# faun-node-connector.net
KiCad netlist of a schematic drawn in EAGLE
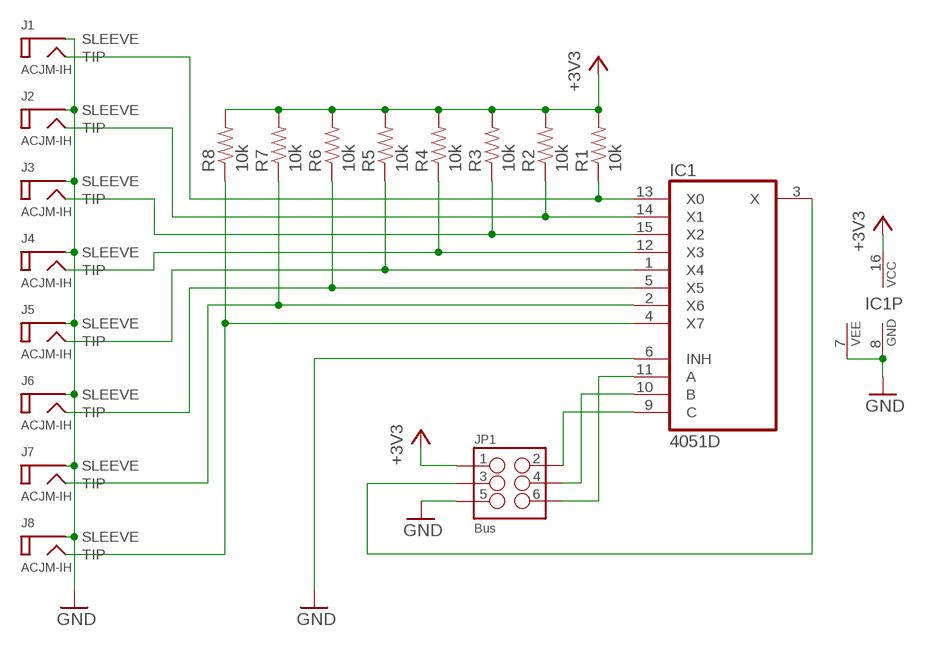
[diagram p0: schematic, sheet 1]

(export (version "E")
  (design (tool "Eeschema 10.0.6"))
  (components
    (comp (ref "IC1")
      (value "4051D")
      (footprint "eagle-import:SO16")
      (libsource (lib "eagle-import") (part "4051D"))
    )
    (comp (ref "J1")
      (value "ACJM-IH")
      (footprint "eagle-import:ACJM-IH")
      (libsource (lib "eagle-import") (part "ACJM-IH"))
    )
    (comp (ref "J2")
      (value "ACJM-IH")
      (footprint "eagle-import:ACJM-IH")
      (libsource (lib "eagle-import") (part "ACJM-IH"))
    )
    (comp (ref "J3")
      (value "ACJM-IH")
      (footprint "eagle-import:ACJM-IH")
      (libsource (lib "eagle-import") (part "ACJM-IH"))
    )
    (comp (ref "J4")
      (value "ACJM-IH")
      (footprint "eagle-import:ACJM-IH")
      (libsource (lib "eagle-import") (part "ACJM-IH"))
    )
    (comp (ref "J5")
      (value "ACJM-IH")
      (footprint "eagle-import:ACJM-IH")
      (libsource (lib "eagle-import") (part "ACJM-IH"))
    )
    (comp (ref "J6")
      (value "ACJM-IH")
      (footprint "eagle-import:ACJM-IH")
      (libsource (lib "eagle-import") (part "ACJM-IH"))
    )
    (comp (ref "J7")
      (value "ACJM-IH")
      (footprint "eagle-import:ACJM-IH")
      (libsource (lib "eagle-import") (part "ACJM-IH"))
    )
    (comp (ref "J8")
      (value "ACJM-IH")
      (footprint "eagle-import:ACJM-IH")
      (libsource (lib "eagle-import") (part "ACJM-IH"))
    )
    (comp (ref "JP1")
      (value "Bus")
      (footprint "eagle-import:2X3")
      (libsource (lib "eagle-import") (part "M03X22X3_SILK_SM"))
    )
    (comp (ref "R1")
      (value "10k")
      (footprint "eagle-import:1206")
      (libsource (lib "eagle-import") (part "RESISTOR1206"))
    )
    (comp (ref "R2")
      (value "10k")
      (footprint "eagle-import:1206")
      (libsource (lib "eagle-import") (part "RESISTOR1206"))
    )
    (comp (ref "R3")
      (value "10k")
      (footprint "eagle-import:1206")
      (libsource (lib "eagle-import") (part "RESISTOR1206"))
    )
    (comp (ref "R4")
      (value "10k")
      (footprint "eagle-import:1206")
      (libsource (lib "eagle-import") (part "RESISTOR1206"))
    )
    (comp (ref "R5")
      (value "10k")
      (footprint "eagle-import:1206")
      (libsource (lib "eagle-import") (part "RESISTOR1206"))
    )
    (comp (ref "R6")
      (value "10k")
      (footprint "eagle-import:1206")
      (libsource (lib "eagle-import") (part "RESISTOR1206"))
    )
    (comp (ref "R7")
      (value "10k")
      (footprint "eagle-import:1206")
      (libsource (lib "eagle-import") (part "RESISTOR1206"))
    )
    (comp (ref "R8")
      (value "10k")
      (footprint "eagle-import:1206")
      (libsource (lib "eagle-import") (part "RESISTOR1206"))
    )
  )
  (nets
    (net (code "1") (name "+3V3") (class "Default")
      (node (ref "IC1") (pin "16") (pinfunction "VCC_16") (pintype "power_in"))
      (node (ref "JP1") (pin "1") (pinfunction "1_1") (pintype "bidirectional"))
      (node (ref "R1") (pin "2") (pinfunction "2_2") (pintype "passive"))
      (node (ref "R2") (pin "2") (pinfunction "2_2") (pintype "passive"))
      (node (ref "R3") (pin "2") (pinfunction "2_2") (pintype "passive"))
      (node (ref "R4") (pin "2") (pinfunction "2_2") (pintype "passive"))
      (node (ref "R5") (pin "2") (pinfunction "2_2") (pintype "passive"))
      (node (ref "R6") (pin "2") (pinfunction "2_2") (pintype "passive"))
      (node (ref "R7") (pin "2") (pinfunction "2_2") (pintype "passive"))
      (node (ref "R8") (pin "2") (pinfunction "2_2") (pintype "passive"))
    )
    (net (code "2") (name "GND") (class "Default")
      (node (ref "IC1") (pin "6") (pinfunction "INH_6") (pintype "input"))
      (node (ref "IC1") (pin "7") (pinfunction "VEE_7") (pintype "power_in"))
      (node (ref "IC1") (pin "8") (pinfunction "GND_8") (pintype "power_in"))
      (node (ref "J1") (pin "SLEEVE@1") (pinfunction "SLEEVE_SLEEVE@1") (pintype "bidirectional"))
      (node (ref "J1") (pin "SLEEVE@2") (pinfunction "SLEEVE_SLEEVE@2") (pintype "bidirectional"))
      (node (ref "J2") (pin "SLEEVE@1") (pinfunction "SLEEVE_SLEEVE@1") (pintype "bidirectional"))
      (node (ref "J2") (pin "SLEEVE@2") (pinfunction "SLEEVE_SLEEVE@2") (pintype "bidirectional"))
      (node (ref "J3") (pin "SLEEVE@1") (pinfunction "SLEEVE_SLEEVE@1") (pintype "bidirectional"))
      (node (ref "J3") (pin "SLEEVE@2") (pinfunction "SLEEVE_SLEEVE@2") (pintype "bidirectional"))
      (node (ref "J4") (pin "SLEEVE@1") (pinfunction "SLEEVE_SLEEVE@1") (pintype "bidirectional"))
      (node (ref "J4") (pin "SLEEVE@2") (pinfunction "SLEEVE_SLEEVE@2") (pintype "bidirectional"))
      (node (ref "J5") (pin "SLEEVE@1") (pinfunction "SLEEVE_SLEEVE@1") (pintype "bidirectional"))
      (node (ref "J5") (pin "SLEEVE@2") (pinfunction "SLEEVE_SLEEVE@2") (pintype "bidirectional"))
      (node (ref "J6") (pin "SLEEVE@1") (pinfunction "SLEEVE_SLEEVE@1") (pintype "bidirectional"))
      (node (ref "J6") (pin "SLEEVE@2") (pinfunction "SLEEVE_SLEEVE@2") (pintype "bidirectional"))
      (node (ref "J7") (pin "SLEEVE@1") (pinfunction "SLEEVE_SLEEVE@1") (pintype "bidirectional"))
      (node (ref "J7") (pin "SLEEVE@2") (pinfunction "SLEEVE_SLEEVE@2") (pintype "bidirectional"))
      (node (ref "J8") (pin "SLEEVE@1") (pinfunction "SLEEVE_SLEEVE@1") (pintype "bidirectional"))
      (node (ref "J8") (pin "SLEEVE@2") (pinfunction "SLEEVE_SLEEVE@2") (pintype "bidirectional"))
      (node (ref "JP1") (pin "5") (pinfunction "5_5") (pintype "bidirectional"))
    )
    (net (code "3") (name "Net-(IC1A-A)") (class "Default")
      (node (ref "IC1") (pin "11") (pinfunction "A_11") (pintype "input"))
      (node (ref "JP1") (pin "6") (pinfunction "6_6") (pintype "bidirectional"))
    )
    (net (code "4") (name "Net-(IC1A-B)") (class "Default")
      (node (ref "IC1") (pin "10") (pinfunction "B_10") (pintype "input"))
      (node (ref "JP1") (pin "4") (pinfunction "4_4") (pintype "bidirectional"))
    )
    (net (code "5") (name "Net-(IC1A-C)") (class "Default")
      (node (ref "IC1") (pin "9") (pinfunction "C_9") (pintype "input"))
      (node (ref "JP1") (pin "2") (pinfunction "2_2") (pintype "bidirectional"))
    )
    (net (code "6") (name "Net-(IC1A-X)") (class "Default")
      (node (ref "IC1") (pin "3") (pinfunction "X_3") (pintype "bidirectional"))
      (node (ref "JP1") (pin "3") (pinfunction "3_3") (pintype "bidirectional"))
    )
    (net (code "7") (name "Net-(IC1A-X0)") (class "Default")
      (node (ref "IC1") (pin "13") (pinfunction "X0_13") (pintype "bidirectional"))
      (node (ref "J1") (pin "TIP@1") (pinfunction "TIP_TIP@1") (pintype "input"))
      (node (ref "J1") (pin "TIP@2") (pinfunction "TIP_TIP@2") (pintype "input"))
      (node (ref "R1") (pin "1") (pinfunction "1_1") (pintype "passive"))
    )
    (net (code "8") (name "Net-(IC1A-X1)") (class "Default")
      (node (ref "IC1") (pin "14") (pinfunction "X1_14") (pintype "bidirectional"))
      (node (ref "J2") (pin "TIP@1") (pinfunction "TIP_TIP@1") (pintype "input"))
      (node (ref "J2") (pin "TIP@2") (pinfunction "TIP_TIP@2") (pintype "input"))
      (node (ref "R2") (pin "1") (pinfunction "1_1") (pintype "passive"))
    )
    (net (code "9") (name "Net-(IC1A-X2)") (class "Default")
      (node (ref "IC1") (pin "15") (pinfunction "X2_15") (pintype "bidirectional"))
      (node (ref "J3") (pin "TIP@1") (pinfunction "TIP_TIP@1") (pintype "input"))
      (node (ref "J3") (pin "TIP@2") (pinfunction "TIP_TIP@2") (pintype "input"))
      (node (ref "R3") (pin "1") (pinfunction "1_1") (pintype "passive"))
    )
    (net (code "10") (name "Net-(IC1A-X3)") (class "Default")
      (node (ref "IC1") (pin "12") (pinfunction "X3_12") (pintype "bidirectional"))
      (node (ref "J4") (pin "TIP@1") (pinfunction "TIP_TIP@1") (pintype "input"))
      (node (ref "J4") (pin "TIP@2") (pinfunction "TIP_TIP@2") (pintype "input"))
      (node (ref "R4") (pin "1") (pinfunction "1_1") (pintype "passive"))
    )
    (net (code "11") (name "Net-(IC1A-X4)") (class "Default")
      (node (ref "IC1") (pin "1") (pinfunction "X4_1") (pintype "bidirectional"))
      (node (ref "J5") (pin "TIP@1") (pinfunction "TIP_TIP@1") (pintype "input"))
      (node (ref "J5") (pin "TIP@2") (pinfunction "TIP_TIP@2") (pintype "input"))
      (node (ref "R5") (pin "1") (pinfunction "1_1") (pintype "passive"))
    )
    (net (code "12") (name "Net-(IC1A-X5)") (class "Default")
      (node (ref "IC1") (pin "5") (pinfunction "X5_5") (pintype "bidirectional"))
      (node (ref "J6") (pin "TIP@1") (pinfunction "TIP_TIP@1") (pintype "input"))
      (node (ref "J6") (pin "TIP@2") (pinfunction "TIP_TIP@2") (pintype "input"))
      (node (ref "R6") (pin "1") (pinfunction "1_1") (pintype "passive"))
    )
    (net (code "13") (name "Net-(IC1A-X6)") (class "Default")
      (node (ref "IC1") (pin "2") (pinfunction "X6_2") (pintype "bidirectional"))
      (node (ref "J7") (pin "TIP@1") (pinfunction "TIP_TIP@1") (pintype "input"))
      (node (ref "J7") (pin "TIP@2") (pinfunction "TIP_TIP@2") (pintype "input"))
      (node (ref "R7") (pin "1") (pinfunction "1_1") (pintype "passive"))
    )
    (net (code "14") (name "Net-(IC1A-X7)") (class "Default")
      (node (ref "IC1") (pin "4") (pinfunction "X7_4") (pintype "bidirectional"))
      (node (ref "J8") (pin "TIP@1") (pinfunction "TIP_TIP@1") (pintype "input"))
      (node (ref "J8") (pin "TIP@2") (pinfunction "TIP_TIP@2") (pintype "input"))
      (node (ref "R8") (pin "1") (pinfunction "1_1") (pintype "passive"))
    )
  )
)
